# photon_at7020_1_rf_test_2.net
KiCad netlist of a schematic drawn in EAGLE
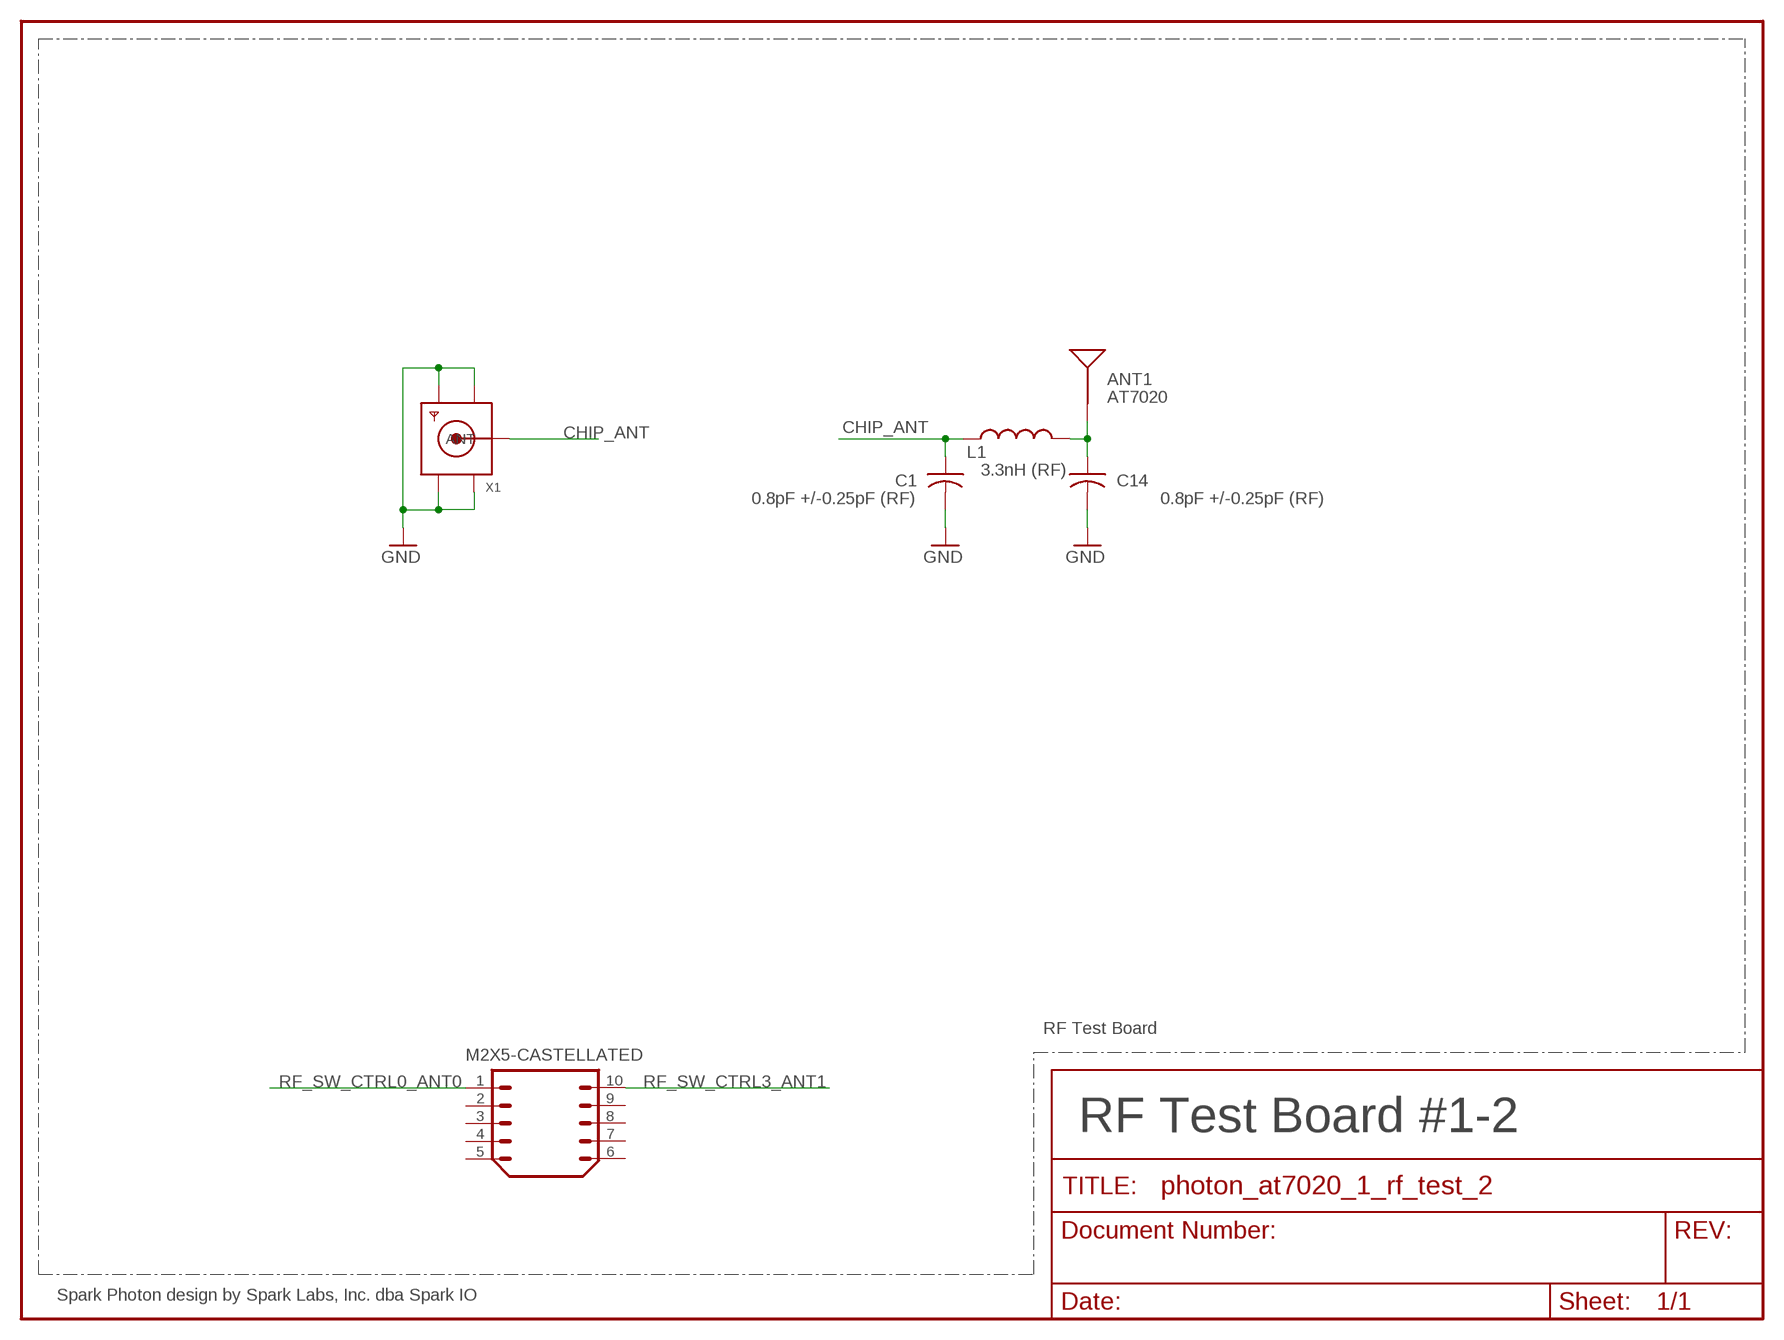
[diagram p0: schematic, sheet 1]

(export (version "E")
  (design (tool "Eeschema 10.0.6"))
  (components
    (comp (ref "ANT1")
      (value "AT7020")
      (footprint "eagle-import:AT7020")
      (libsource (lib "eagle-import") (part "AT7020"))
    )
    (comp (ref "C1")
      (value "0.8pF +/-0.25pF (RF)")
      (footprint "eagle-import:C0402_B")
      (libsource (lib "eagle-import") (part "C-US"))
    )
    (comp (ref "C14")
      (value "0.8pF +/-0.25pF (RF)")
      (footprint "eagle-import:C0402_B")
      (libsource (lib "eagle-import") (part "C-US"))
    )
    (comp (ref "L1")
      (value "3.3nH (RF)")
      (footprint "eagle-import:L0402_B")
      (libsource (lib "eagle-import") (part "INDUCTOR"))
    )
    (comp (ref "M2X5-CASTELLATED")
      (value "M2X5")
      (footprint "eagle-import:2X5-CASTELLATED")
      (libsource (lib "eagle-import") (part "M2X5"))
    )
    (comp (ref "X1")
      (value "SMACONNECTOR_EDGE")
      (footprint "eagle-import:SMA_EDGELAUNCH")
      (libsource (lib "eagle-import") (part "SMACONNECTOR_EDGE"))
    )
  )
  (nets
    (net (code "1") (name "/CHIP_ANT") (class "Default")
      (node (ref "C1") (pin "1") (pinfunction "1_1") (pintype "passive"))
      (node (ref "L1") (pin "1") (pinfunction "1_1") (pintype "passive"))
      (node (ref "X1") (pin "P") (pinfunction "ANT_P") (pintype "bidirectional"))
    )
    (net (code "2") (name "/RF_SW_CTRL0_ANT0") (class "Default")
      (node (ref "M2X5-CASTELLATED") (pin "1") (pinfunction "1_1") (pintype "passive"))
    )
    (net (code "3") (name "/RF_SW_CTRL3_ANT1") (class "Default")
      (node (ref "M2X5-CASTELLATED") (pin "10") (pinfunction "10_10") (pintype "passive"))
    )
    (net (code "4") (name "GND") (class "Default")
      (node (ref "C1") (pin "2") (pinfunction "2_2") (pintype "passive"))
      (node (ref "C14") (pin "2") (pinfunction "2_2") (pintype "passive"))
      (node (ref "X1") (pin "GND@1") (pinfunction "GND4_GND@1") (pintype "power_in"))
      (node (ref "X1") (pin "GND@2") (pinfunction "GND3_GND@2") (pintype "power_in"))
      (node (ref "X1") (pin "GND@3") (pinfunction "GND2_GND@3") (pintype "power_in"))
      (node (ref "X1") (pin "GND@4") (pinfunction "GND1_GND@4") (pintype "power_in"))
    )
    (net (code "5") (name "Net-(ANT1-SIGNAL)") (class "Default")
      (node (ref "ANT1") (pin "1") (pinfunction "SIGNAL_1") (pintype "bidirectional"))
      (node (ref "C14") (pin "1") (pinfunction "1_1") (pintype "passive"))
      (node (ref "L1") (pin "2") (pinfunction "2_2") (pintype "passive"))
    )
    (net (code "6") (name "unconnected-(M2X5-CASTELLATED-Pad2)") (class "Default")
      (node (ref "M2X5-CASTELLATED") (pin "2") (pinfunction "2_2") (pintype "passive"))
    )
    (net (code "7") (name "unconnected-(M2X5-CASTELLATED-Pad3)") (class "Default")
      (node (ref "M2X5-CASTELLATED") (pin "3") (pinfunction "3_3") (pintype "passive"))
    )
    (net (code "8") (name "unconnected-(M2X5-CASTELLATED-Pad4)") (class "Default")
      (node (ref "M2X5-CASTELLATED") (pin "4") (pinfunction "4_4") (pintype "passive"))
    )
    (net (code "9") (name "unconnected-(M2X5-CASTELLATED-Pad5)") (class "Default")
      (node (ref "M2X5-CASTELLATED") (pin "5") (pinfunction "5_5") (pintype "passive"))
    )
    (net (code "10") (name "unconnected-(M2X5-CASTELLATED-Pad6)") (class "Default")
      (node (ref "M2X5-CASTELLATED") (pin "6") (pinfunction "6_6") (pintype "passive"))
    )
    (net (code "11") (name "unconnected-(M2X5-CASTELLATED-Pad7)") (class "Default")
      (node (ref "M2X5-CASTELLATED") (pin "7") (pinfunction "7_7") (pintype "passive"))
    )
    (net (code "12") (name "unconnected-(M2X5-CASTELLATED-Pad8)") (class "Default")
      (node (ref "M2X5-CASTELLATED") (pin "8") (pinfunction "8_8") (pintype "passive"))
    )
    (net (code "13") (name "unconnected-(M2X5-CASTELLATED-Pad9)") (class "Default")
      (node (ref "M2X5-CASTELLATED") (pin "9") (pinfunction "9_9") (pintype "passive"))
    )
  )
)
